# Rover_PI_hat.net
KiCad netlist of a schematic drawn in Altium Designer
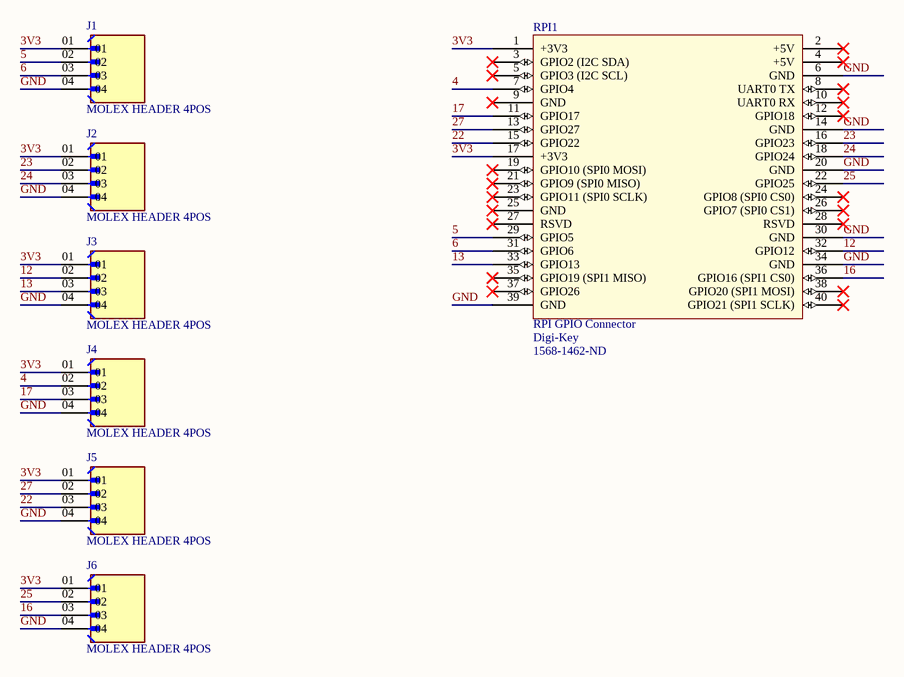
[diagram p0: Rover_PI_hat.SchDoc]

(export (version "E")
  (design (tool "Eeschema 10.0.6"))
  (components
    (comp (ref "J1")
      (value "MOLEX HEADER 4POS")
      (footprint "MOLEX_35362-0450")
      (description "Connector Header Through Hole 4 position 0.079 (2.00mm)")
      (fields (field (name "MP") "35362-0450") (field (name "MF") "Molex"))
      (libsource (lib "35362-0450") (part "35362-0450"))
    )
    (comp (ref "J2")
      (value "MOLEX HEADER 4POS")
      (footprint "MOLEX_35362-0450")
      (description "Connector Header Through Hole 4 position 0.079 (2.00mm)")
      (fields (field (name "MP") "35362-0450") (field (name "MF") "Molex"))
      (libsource (lib "35362-0450") (part "35362-0450"))
    )
    (comp (ref "J3")
      (value "MOLEX HEADER 4POS")
      (footprint "MOLEX_35362-0450")
      (description "Connector Header Through Hole 4 position 0.079 (2.00mm)")
      (fields (field (name "MP") "35362-0450") (field (name "MF") "Molex"))
      (libsource (lib "35362-0450") (part "35362-0450"))
    )
    (comp (ref "J4")
      (value "MOLEX HEADER 4POS")
      (footprint "MOLEX_35362-0450")
      (description "Connector Header Through Hole 4 position 0.079 (2.00mm)")
      (fields (field (name "MP") "35362-0450") (field (name "MF") "Molex"))
      (libsource (lib "35362-0450") (part "35362-0450"))
    )
    (comp (ref "J5")
      (value "MOLEX HEADER 4POS")
      (footprint "MOLEX_35362-0450")
      (description "Connector Header Through Hole 4 position 0.079 (2.00mm)")
      (fields (field (name "MP") "35362-0450") (field (name "MF") "Molex"))
      (libsource (lib "35362-0450") (part "35362-0450"))
    )
    (comp (ref "J6")
      (value "MOLEX HEADER 4POS")
      (footprint "MOLEX_35362-0450")
      (description "Connector Header Through Hole 4 position 0.079 (2.00mm)")
      (fields (field (name "MP") "35362-0450") (field (name "MF") "Molex"))
      (libsource (lib "35362-0450") (part "35362-0450"))
    )
    (comp (ref "RPI1")
      (value "RPI GPIO Connector")
      (footprint "rpi")
      (description "GPIO Header for Raspberry Pi A+/B+/Pi 2/Pi 3 - 2x20")
      (fields
        (field (name "MANUFACTURER") "SparkFun Electronics")
        (field (name "MANUFACTURER PART NUMBER") "PRT-14017")
        (field (name "SUPPLIER 1") "Digi-Key")
        (field (name "SUPPLIER PART NUMBER 1") "1568-1462-ND")
      )
      (libsource (lib "rpi") (part "rpi connector"))
    )
  )
  (nets
    (net (code "1") (name "/3V3") (class "Default")
      (node (ref "J1") (pin "01") (pinfunction "01_01") (pintype "passive"))
      (node (ref "J2") (pin "01") (pinfunction "01_01") (pintype "passive"))
      (node (ref "J3") (pin "01") (pinfunction "01_01") (pintype "passive"))
      (node (ref "J4") (pin "01") (pinfunction "01_01") (pintype "passive"))
      (node (ref "J5") (pin "01") (pinfunction "01_01") (pintype "passive"))
      (node (ref "J6") (pin "01") (pinfunction "01_01") (pintype "passive"))
      (node (ref "RPI1") (pin "1") (pinfunction "+3V3_1") (pintype "power_in"))
      (node (ref "RPI1") (pin "17") (pinfunction "+3V3_17") (pintype "power_in"))
    )
    (net (code "2") (name "/4") (class "Default")
      (node (ref "J4") (pin "02") (pinfunction "02_02") (pintype "passive"))
      (node (ref "RPI1") (pin "7") (pinfunction "GPIO4_7") (pintype "bidirectional"))
    )
    (net (code "3") (name "/5") (class "Default")
      (node (ref "J1") (pin "02") (pinfunction "02_02") (pintype "passive"))
      (node (ref "RPI1") (pin "29") (pinfunction "GPIO5_29") (pintype "bidirectional"))
    )
    (net (code "4") (name "/6") (class "Default")
      (node (ref "J1") (pin "03") (pinfunction "03_03") (pintype "passive"))
      (node (ref "RPI1") (pin "31") (pinfunction "GPIO6_31") (pintype "bidirectional"))
    )
    (net (code "5") (name "/12") (class "Default")
      (node (ref "J3") (pin "02") (pinfunction "02_02") (pintype "passive"))
      (node (ref "RPI1") (pin "32") (pinfunction "GPIO12_32") (pintype "bidirectional"))
    )
    (net (code "6") (name "/13") (class "Default")
      (node (ref "J3") (pin "03") (pinfunction "03_03") (pintype "passive"))
      (node (ref "RPI1") (pin "33") (pinfunction "GPIO13_33") (pintype "bidirectional"))
    )
    (net (code "7") (name "/16") (class "Default")
      (node (ref "J6") (pin "03") (pinfunction "03_03") (pintype "passive"))
      (node (ref "RPI1") (pin "36") (pinfunction "GPIO16_(SPI1_CS0)_36") (pintype "bidirectional"))
    )
    (net (code "8") (name "/17") (class "Default")
      (node (ref "J4") (pin "03") (pinfunction "03_03") (pintype "passive"))
      (node (ref "RPI1") (pin "11") (pinfunction "GPIO17_11") (pintype "bidirectional"))
    )
    (net (code "9") (name "/22") (class "Default")
      (node (ref "J5") (pin "03") (pinfunction "03_03") (pintype "passive"))
      (node (ref "RPI1") (pin "15") (pinfunction "GPIO22_15") (pintype "bidirectional"))
    )
    (net (code "10") (name "/23") (class "Default")
      (node (ref "J2") (pin "02") (pinfunction "02_02") (pintype "passive"))
      (node (ref "RPI1") (pin "16") (pinfunction "GPIO23_16") (pintype "bidirectional"))
    )
    (net (code "11") (name "/24") (class "Default")
      (node (ref "J2") (pin "03") (pinfunction "03_03") (pintype "passive"))
      (node (ref "RPI1") (pin "18") (pinfunction "GPIO24_18") (pintype "bidirectional"))
    )
    (net (code "12") (name "/25") (class "Default")
      (node (ref "J6") (pin "02") (pinfunction "02_02") (pintype "passive"))
      (node (ref "RPI1") (pin "22") (pinfunction "GPIO25_22") (pintype "bidirectional"))
    )
    (net (code "13") (name "/27") (class "Default")
      (node (ref "J5") (pin "02") (pinfunction "02_02") (pintype "passive"))
      (node (ref "RPI1") (pin "13") (pinfunction "GPIO27_13") (pintype "bidirectional"))
    )
    (net (code "14") (name "/GND") (class "Default")
      (node (ref "J1") (pin "04") (pinfunction "04_04") (pintype "passive"))
      (node (ref "J2") (pin "04") (pinfunction "04_04") (pintype "passive"))
      (node (ref "J3") (pin "04") (pinfunction "04_04") (pintype "passive"))
      (node (ref "J4") (pin "04") (pinfunction "04_04") (pintype "passive"))
      (node (ref "J5") (pin "04") (pinfunction "04_04") (pintype "passive"))
      (node (ref "J6") (pin "04") (pinfunction "04_04") (pintype "passive"))
      (node (ref "RPI1") (pin "14") (pinfunction "GND_14") (pintype "power_in"))
      (node (ref "RPI1") (pin "20") (pinfunction "GND_20") (pintype "power_in"))
      (node (ref "RPI1") (pin "30") (pinfunction "GND_30") (pintype "power_in"))
      (node (ref "RPI1") (pin "34") (pinfunction "GND_34") (pintype "passive"))
      (node (ref "RPI1") (pin "39") (pinfunction "GND_39") (pintype "power_in"))
      (node (ref "RPI1") (pin "6") (pinfunction "GND_6") (pintype "power_in"))
    )
    (net (code "15") (name "unconnected-(RPI1-+5V-Pad2)") (class "Default")
      (node (ref "RPI1") (pin "2") (pinfunction "+5V_2") (pintype "power_in+no_connect"))
    )
    (net (code "16") (name "unconnected-(RPI1-+5V-Pad4)") (class "Default")
      (node (ref "RPI1") (pin "4") (pinfunction "+5V_4") (pintype "power_in+no_connect"))
    )
    (net (code "17") (name "unconnected-(RPI1-GND-Pad9)") (class "Default")
      (node (ref "RPI1") (pin "9") (pinfunction "GND_9") (pintype "power_in+no_connect"))
    )
    (net (code "18") (name "unconnected-(RPI1-GND-Pad25)") (class "Default")
      (node (ref "RPI1") (pin "25") (pinfunction "GND_25") (pintype "power_in+no_connect"))
    )
    (net (code "19") (name "unconnected-(RPI1-GPIO2_(I2C_SDA)-Pad3)") (class "Default")
      (node (ref "RPI1") (pin "3") (pinfunction "GPIO2_(I2C_SDA)_3") (pintype "bidirectional+no_connect"))
    )
    (net (code "20") (name "unconnected-(RPI1-GPIO3_(I2C_SCL)-Pad5)") (class "Default")
      (node (ref "RPI1") (pin "5") (pinfunction "GPIO3_(I2C_SCL)_5") (pintype "bidirectional+no_connect"))
    )
    (net (code "21") (name "unconnected-(RPI1-GPIO7_(SPI0_CS1)-Pad26)") (class "Default")
      (node (ref "RPI1") (pin "26") (pinfunction "GPIO7_(SPI0_CS1)_26") (pintype "bidirectional+no_connect"))
    )
    (net (code "22") (name "unconnected-(RPI1-GPIO8_(SPI0_CS0)-Pad24)") (class "Default")
      (node (ref "RPI1") (pin "24") (pinfunction "GPIO8_(SPI0_CS0)_24") (pintype "bidirectional+no_connect"))
    )
    (net (code "23") (name "unconnected-(RPI1-GPIO9_(SPI0_MISO)-Pad21)") (class "Default")
      (node (ref "RPI1") (pin "21") (pinfunction "GPIO9_(SPI0_MISO)_21") (pintype "bidirectional+no_connect"))
    )
    (net (code "24") (name "unconnected-(RPI1-GPIO10_(SPI0_MOSI)-Pad19)") (class "Default")
      (node (ref "RPI1") (pin "19") (pinfunction "GPIO10_(SPI0_MOSI)_19") (pintype "bidirectional+no_connect"))
    )
    (net (code "25") (name "unconnected-(RPI1-GPIO11_(SPI0_SCLK)-Pad23)") (class "Default")
      (node (ref "RPI1") (pin "23") (pinfunction "GPIO11_(SPI0_SCLK)_23") (pintype "bidirectional+no_connect"))
    )
    (net (code "26") (name "unconnected-(RPI1-GPIO18-Pad12)") (class "Default")
      (node (ref "RPI1") (pin "12") (pinfunction "GPIO18_12") (pintype "bidirectional+no_connect"))
    )
    (net (code "27") (name "unconnected-(RPI1-GPIO19_(SPI1_MISO)-Pad35)") (class "Default")
      (node (ref "RPI1") (pin "35") (pinfunction "GPIO19_(SPI1_MISO)_35") (pintype "bidirectional+no_connect"))
    )
    (net (code "28") (name "unconnected-(RPI1-GPIO20_(SPI1_MOSI)-Pad38)") (class "Default")
      (node (ref "RPI1") (pin "38") (pinfunction "GPIO20_(SPI1_MOSI)_38") (pintype "bidirectional+no_connect"))
    )
    (net (code "29") (name "unconnected-(RPI1-GPIO21_(SPI1_SCLK)-Pad40)") (class "Default")
      (node (ref "RPI1") (pin "40") (pinfunction "GPIO21_(SPI1_SCLK)_40") (pintype "bidirectional+no_connect"))
    )
    (net (code "30") (name "unconnected-(RPI1-GPIO26-Pad37)") (class "Default")
      (node (ref "RPI1") (pin "37") (pinfunction "GPIO26_37") (pintype "bidirectional+no_connect"))
    )
    (net (code "31") (name "unconnected-(RPI1-RSVD-Pad27)") (class "Default")
      (node (ref "RPI1") (pin "27") (pinfunction "RSVD_27") (pintype "passive+no_connect"))
    )
    (net (code "32") (name "unconnected-(RPI1-RSVD-Pad28)") (class "Default")
      (node (ref "RPI1") (pin "28") (pinfunction "RSVD_28") (pintype "passive+no_connect"))
    )
    (net (code "33") (name "unconnected-(RPI1-UART0_RX-Pad10)") (class "Default")
      (node (ref "RPI1") (pin "10") (pinfunction "UART0_RX_10") (pintype "bidirectional+no_connect"))
    )
    (net (code "34") (name "unconnected-(RPI1-UART0_TX-Pad8)") (class "Default")
      (node (ref "RPI1") (pin "8") (pinfunction "UART0_TX_8") (pintype "bidirectional+no_connect"))
    )
  )
)
